# SparkFun_Qwiic_12_Bit_ADC_-_4_Channel_AD.net
KiCad netlist of a schematic drawn in EAGLE
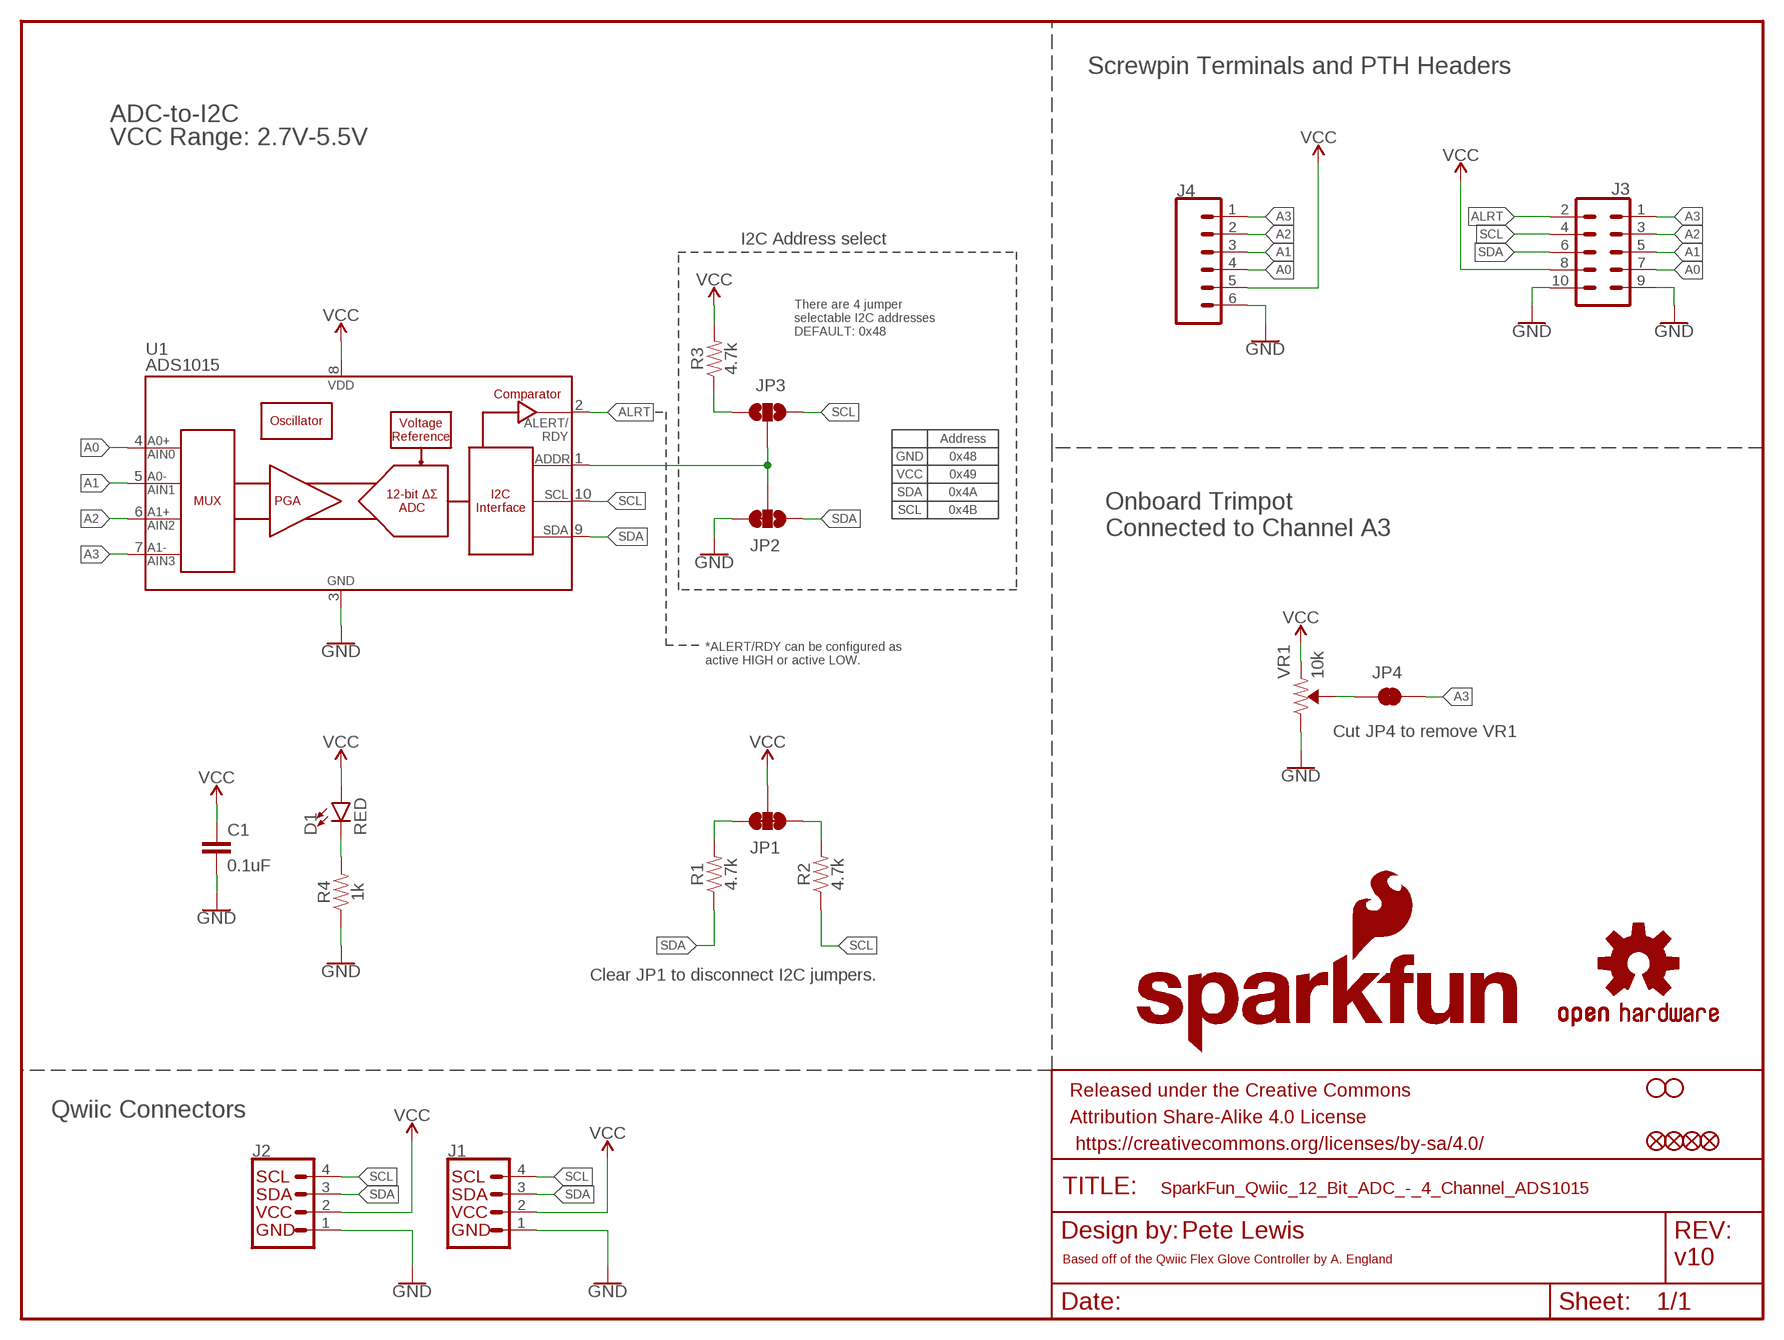
[diagram p0: schematic, sheet 1]

(export (version "E")
  (design (tool "Eeschema 10.0.6"))
  (components
    (comp (ref "C1")
      (value "0.1uF")
      (footprint "eagle-import:0603")
      (libsource (lib "eagle-import") (part "0.1UF-0603-25V-(+80/-20%)"))
    )
    (comp (ref "D1")
      (value "RED")
      (footprint "eagle-import:LED-0603")
      (libsource (lib "eagle-import") (part "LED-RED0603"))
    )
    (comp (ref "FD1")
      (value "FIDUCIALUFIDUCIAL")
      (footprint "eagle-import:FIDUCIAL-MICRO")
      (libsource (lib "eagle-import") (part "FIDUCIALUFIDUCIAL"))
    )
    (comp (ref "FD2")
      (value "FIDUCIALUFIDUCIAL")
      (footprint "eagle-import:FIDUCIAL-MICRO")
      (libsource (lib "eagle-import") (part "FIDUCIALUFIDUCIAL"))
    )
    (comp (ref "FD3")
      (value "FIDUCIALUFIDUCIAL")
      (footprint "eagle-import:FIDUCIAL-MICRO")
      (libsource (lib "eagle-import") (part "FIDUCIALUFIDUCIAL"))
    )
    (comp (ref "FD4")
      (value "FIDUCIALUFIDUCIAL")
      (footprint "eagle-import:FIDUCIAL-MICRO")
      (libsource (lib "eagle-import") (part "FIDUCIALUFIDUCIAL"))
    )
    (comp (ref "FRAME1")
      (value "FRAME-LETTER")
      (footprint "eagle-import:CREATIVE_COMMONS")
      (libsource (lib "eagle-import") (part "FRAME-LETTER"))
    )
    (comp (ref "H1")
      (value "STAND-OFF")
      (footprint "eagle-import:STAND-OFF")
      (libsource (lib "eagle-import") (part "STAND-OFF"))
    )
    (comp (ref "H2")
      (value "STAND-OFF")
      (footprint "eagle-import:STAND-OFF")
      (libsource (lib "eagle-import") (part "STAND-OFF"))
    )
    (comp (ref "J1")
      (value "QWIIC_CONNECTORJS-1MM")
      (footprint "eagle-import:JST04_1MM_RA")
      (libsource (lib "eagle-import") (part "QWIIC_CONNECTORJS-1MM"))
    )
    (comp (ref "J2")
      (value "QWIIC_CONNECTORJS-1MM")
      (footprint "eagle-import:JST04_1MM_RA")
      (libsource (lib "eagle-import") (part "QWIIC_CONNECTORJS-1MM"))
    )
    (comp (ref "J3")
      (value "CONN_05X2NO_SILK")
      (footprint "eagle-import:2X5_NOSILK")
      (libsource (lib "eagle-import") (part "CONN_05X2NO_SILK"))
    )
    (comp (ref "J4")
      (value "Screw Pin")
      (footprint "eagle-import:SCREWTERMINAL-3.5MM-6")
      (libsource (lib "eagle-import") (part "CONN_063.5MM-6"))
    )
    (comp (ref "JP1")
      (value "JUMPER-SMT_3_2-NC_TRACE_NO-SILK")
      (footprint "eagle-import:SMT-JUMPER_3_2-NC_TRACE_NO-SILK")
      (libsource (lib "eagle-import") (part "JUMPER-SMT_3_2-NC_TRACE_NO-SILK"))
    )
    (comp (ref "JP2")
      (value "JUMPER-SMT_3_1-NC_TRACE_NO-SILK")
      (footprint "eagle-import:SMT-JUMPER_3_1-NC_TRACE_NO-SILK")
      (libsource (lib "eagle-import") (part "JUMPER-SMT_3_1-NC_TRACE_NO-SILK"))
    )
    (comp (ref "JP3")
      (value "JUMPER-SMT_3_NO_NO_SILK")
      (footprint "eagle-import:SMT-JUMPER_3_0-NO_TRACE_NO-SILK")
      (libsource (lib "eagle-import") (part "JUMPER-SMT_3_NO_NO_SILK"))
    )
    (comp (ref "JP4")
      (value "JUMPER-SMT_2_NC_TRACE_SILK")
      (footprint "eagle-import:SMT-JUMPER_2_NC_TRACE_SILK")
      (libsource (lib "eagle-import") (part "JUMPER-SMT_2_NC_TRACE_SILK"))
    )
    (comp (ref "LOGO1")
      (value "SFE_LOGO_NAME.1_INCH")
      (footprint "eagle-import:SFE_LOGO_NAME_.1")
      (libsource (lib "eagle-import") (part "SFE_LOGO_NAME.1_INCH"))
    )
    (comp (ref "LOGO2")
      (value "OSHW-LOGOS")
      (footprint "eagle-import:OSHW-LOGO-S")
      (libsource (lib "eagle-import") (part "OSHW-LOGOS"))
    )
    (comp (ref "LOGO3")
      (value "SFE_LOGO_FLAME.1_INCH")
      (footprint "eagle-import:SFE_LOGO_FLAME_.1")
      (libsource (lib "eagle-import") (part "SFE_LOGO_FLAME.1_INCH"))
    )
    (comp (ref "R1")
      (value "4.7k")
      (footprint "eagle-import:0603")
      (libsource (lib "eagle-import") (part "4.7KOHM-0603-1/10W-1%"))
    )
    (comp (ref "R2")
      (value "4.7k")
      (footprint "eagle-import:0603")
      (libsource (lib "eagle-import") (part "4.7KOHM-0603-1/10W-1%"))
    )
    (comp (ref "R3")
      (value "4.7k")
      (footprint "eagle-import:0603")
      (libsource (lib "eagle-import") (part "4.7KOHM-0603-1/10W-1%"))
    )
    (comp (ref "R4")
      (value "1k")
      (footprint "eagle-import:0603")
      (libsource (lib "eagle-import") (part "1KOHM-0603-1/10W-1%"))
    )
    (comp (ref "U1")
      (value "ADS1015")
      (footprint "eagle-import:MSOP10")
      (libsource (lib "eagle-import") (part "ADS1015"))
    )
    (comp (ref "VR1")
      (value "10k")
      (footprint "eagle-import:TRIMPOT-SMD-3MM-CLOSED")
      (libsource (lib "eagle-import") (part "TRIMPOT-SMD-3MM-CLOSED-1/8W-20%"))
    )
  )
  (nets
    (net (code "1") (name "A0") (class "Default")
      (node (ref "J3") (pin "7") (pinfunction "7_7") (pintype "passive"))
      (node (ref "J4") (pin "4") (pinfunction "4_4") (pintype "passive"))
      (node (ref "U1") (pin "4") (pinfunction "AIN0_4") (pintype "bidirectional"))
    )
    (net (code "2") (name "A1") (class "Default")
      (node (ref "J3") (pin "5") (pinfunction "5_5") (pintype "passive"))
      (node (ref "J4") (pin "3") (pinfunction "3_3") (pintype "passive"))
      (node (ref "U1") (pin "5") (pinfunction "AIN1_5") (pintype "bidirectional"))
    )
    (net (code "3") (name "A2") (class "Default")
      (node (ref "J3") (pin "3") (pinfunction "3_3") (pintype "passive"))
      (node (ref "J4") (pin "2") (pinfunction "2_2") (pintype "passive"))
      (node (ref "U1") (pin "6") (pinfunction "AIN2_6") (pintype "bidirectional"))
    )
    (net (code "4") (name "A3") (class "Default")
      (node (ref "J3") (pin "1") (pinfunction "1_1") (pintype "passive"))
      (node (ref "J4") (pin "1") (pinfunction "1_1") (pintype "passive"))
      (node (ref "JP4") (pin "2") (pinfunction "2_2") (pintype "passive"))
      (node (ref "U1") (pin "7") (pinfunction "AIN3_7") (pintype "bidirectional"))
    )
    (net (code "5") (name "ALRT") (class "Default")
      (node (ref "J3") (pin "2") (pinfunction "2_2") (pintype "passive"))
      (node (ref "U1") (pin "2") (pinfunction "ALERT/RDY_2") (pintype "bidirectional"))
    )
    (net (code "6") (name "GND") (class "Default")
      (node (ref "C1") (pin "2") (pinfunction "2_2") (pintype "passive"))
      (node (ref "J1") (pin "1") (pinfunction "1_1") (pintype "power_in"))
      (node (ref "J2") (pin "1") (pinfunction "1_1") (pintype "power_in"))
      (node (ref "J3") (pin "10") (pinfunction "10_10") (pintype "passive"))
      (node (ref "J3") (pin "9") (pinfunction "9_9") (pintype "passive"))
      (node (ref "J4") (pin "6") (pinfunction "6_6") (pintype "passive"))
      (node (ref "JP2") (pin "3") (pinfunction "3_3") (pintype "passive"))
      (node (ref "R4") (pin "1") (pinfunction "1_1") (pintype "passive"))
      (node (ref "U1") (pin "3") (pinfunction "VSS_3") (pintype "bidirectional"))
      (node (ref "VR1") (pin "3") (pinfunction "CW_3") (pintype "passive"))
    )
    (net (code "7") (name "Net-(D1-PadC)") (class "Default")
      (node (ref "D1") (pin "C") (pinfunction "C_C") (pintype "passive"))
      (node (ref "R4") (pin "2") (pinfunction "2_2") (pintype "passive"))
    )
    (net (code "8") (name "Net-(JP1-Pad1)") (class "Default")
      (node (ref "JP1") (pin "1") (pinfunction "1_1") (pintype "passive"))
      (node (ref "R2") (pin "2") (pinfunction "2_2") (pintype "passive"))
    )
    (net (code "9") (name "Net-(JP1-Pad3)") (class "Default")
      (node (ref "JP1") (pin "3") (pinfunction "3_3") (pintype "passive"))
      (node (ref "R1") (pin "2") (pinfunction "2_2") (pintype "passive"))
    )
    (net (code "10") (name "Net-(JP3-Pad1)") (class "Default")
      (node (ref "JP3") (pin "1") (pinfunction "1_1") (pintype "passive"))
      (node (ref "R3") (pin "1") (pinfunction "1_1") (pintype "passive"))
    )
    (net (code "11") (name "Net-(U1-ADDR)") (class "Default")
      (node (ref "JP2") (pin "2") (pinfunction "2_2") (pintype "passive"))
      (node (ref "JP3") (pin "2") (pinfunction "2_2") (pintype "passive"))
      (node (ref "U1") (pin "1") (pinfunction "ADDR_1") (pintype "bidirectional"))
    )
    (net (code "12") (name "Net-(VR1-WIPER)") (class "Default")
      (node (ref "JP4") (pin "1") (pinfunction "1_1") (pintype "passive"))
      (node (ref "VR1") (pin "2") (pinfunction "WIPER_2") (pintype "passive"))
    )
    (net (code "13") (name "SCL") (class "Default")
      (node (ref "J1") (pin "4") (pinfunction "4_4") (pintype "passive"))
      (node (ref "J2") (pin "4") (pinfunction "4_4") (pintype "passive"))
      (node (ref "J3") (pin "4") (pinfunction "4_4") (pintype "passive"))
      (node (ref "JP3") (pin "3") (pinfunction "3_3") (pintype "passive"))
      (node (ref "R2") (pin "1") (pinfunction "1_1") (pintype "passive"))
      (node (ref "U1") (pin "10") (pinfunction "SCL_10") (pintype "bidirectional"))
    )
    (net (code "14") (name "SDA") (class "Default")
      (node (ref "J1") (pin "3") (pinfunction "3_3") (pintype "passive"))
      (node (ref "J2") (pin "3") (pinfunction "3_3") (pintype "passive"))
      (node (ref "J3") (pin "6") (pinfunction "6_6") (pintype "passive"))
      (node (ref "JP2") (pin "1") (pinfunction "1_1") (pintype "passive"))
      (node (ref "R1") (pin "1") (pinfunction "1_1") (pintype "passive"))
      (node (ref "U1") (pin "9") (pinfunction "SDA_9") (pintype "bidirectional"))
    )
    (net (code "15") (name "VCC") (class "Default")
      (node (ref "C1") (pin "1") (pinfunction "1_1") (pintype "passive"))
      (node (ref "D1") (pin "A") (pinfunction "A_A") (pintype "passive"))
      (node (ref "J1") (pin "2") (pinfunction "2_2") (pintype "power_in"))
      (node (ref "J2") (pin "2") (pinfunction "2_2") (pintype "power_in"))
      (node (ref "J3") (pin "8") (pinfunction "8_8") (pintype "passive"))
      (node (ref "J4") (pin "5") (pinfunction "5_5") (pintype "passive"))
      (node (ref "JP1") (pin "2") (pinfunction "2_2") (pintype "passive"))
      (node (ref "R3") (pin "2") (pinfunction "2_2") (pintype "passive"))
      (node (ref "U1") (pin "8") (pinfunction "VDD_8") (pintype "bidirectional"))
      (node (ref "VR1") (pin "1") (pinfunction "CCW_1") (pintype "passive"))
    )
  )
)
